# Controller.net
KiCad netlist of a schematic drawn in Altium Designer
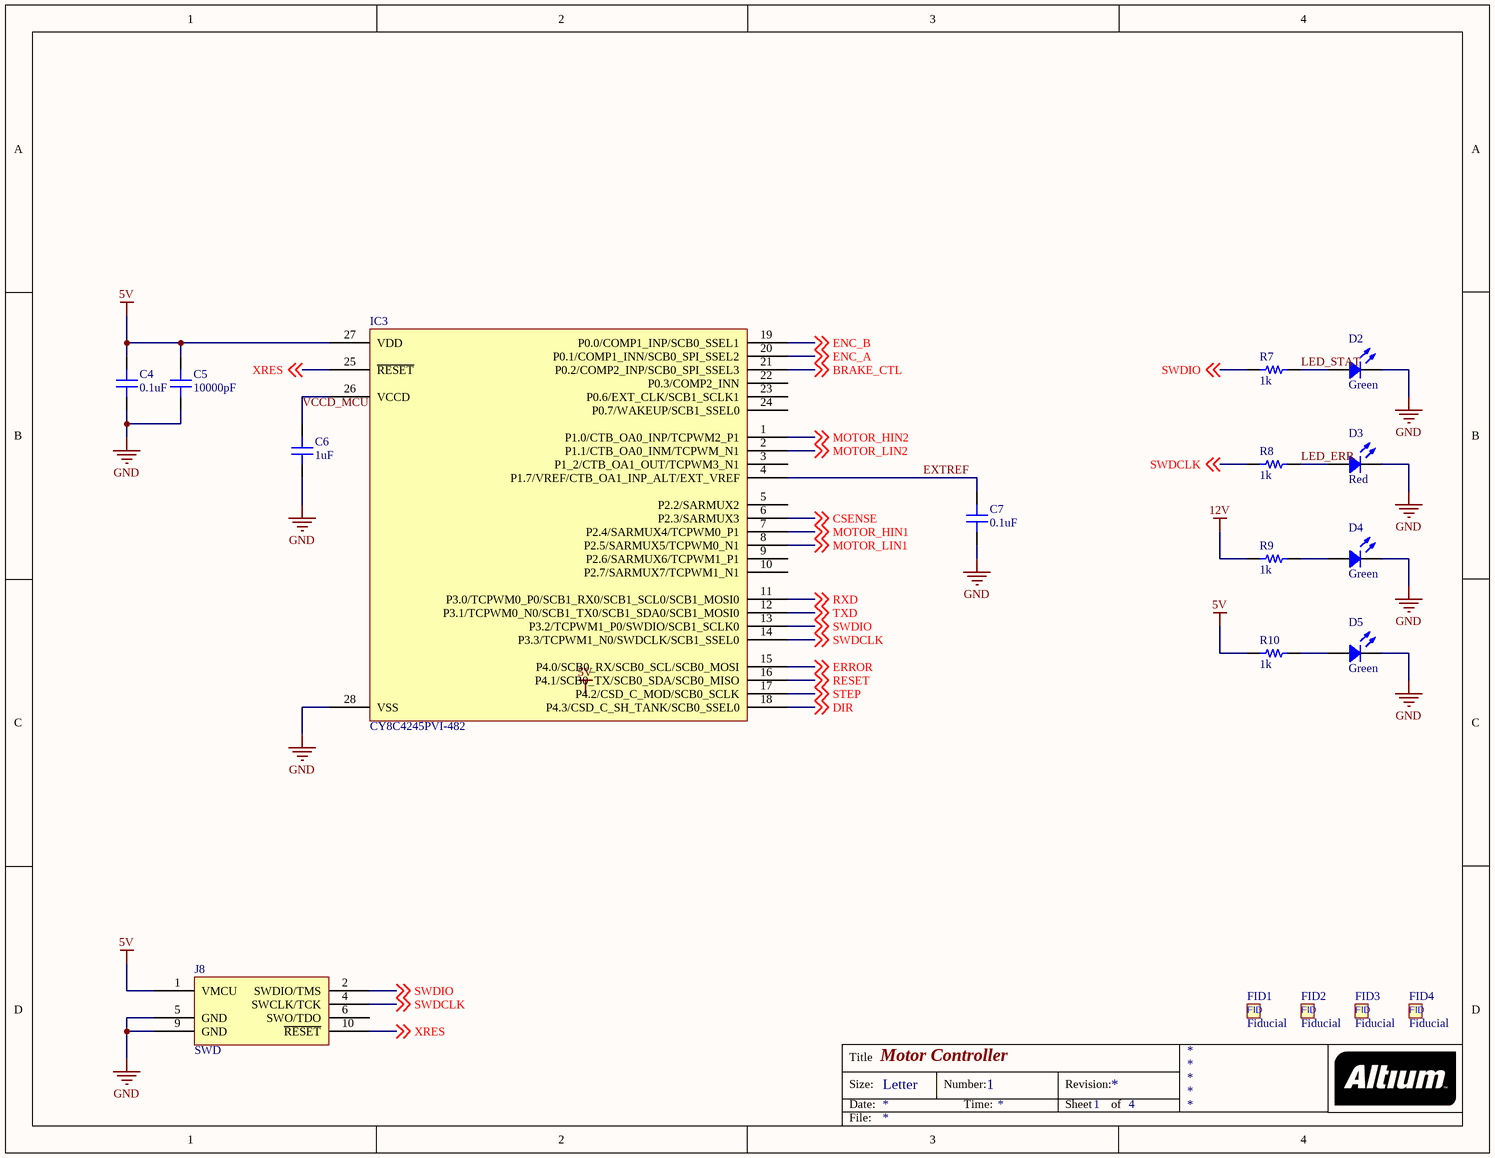
[diagram p0: Controller.SchDoc]

(export (version "E")
  (design (tool "Eeschema 10.0.6"))
  (components
    (comp (ref "C4")
      (value "0.1uF")
      (footprint "CAP 0603/1608")
      (description "CAP CER 0.1UF 16V X7R 0603")
      (fields (field (name "PART NUMBER") "CC0603KPX7R7BB104") (field (name "MANUFACTURER") "Yageo"))
      (libsource (lib "Celestial Library Database") (part "Capacitor"))
    )
    (comp (ref "C5")
      (value "10000pF")
      (footprint "CAP 0603/1608")
      (description "CAP CER 10000PF 50V X7R 0603")
      (fields
        (field (name "PART NUMBER") "CL10B103KB8NCNC")
        (field (name "MANUFACTURER") "Samsung Electro-Mechanics America, Inc.")
      )
      (libsource (lib "Celestial Library Database") (part "Capacitor"))
    )
    (comp (ref "C6")
      (value "1uF")
      (footprint "CAP 0603/1608")
      (description "CAP CER 1UF 16V Y5V 0603")
      (fields (field (name "PART NUMBER") "CC0603ZRY5V7BB105") (field (name "MANUFACTURER") "Yageo"))
      (libsource (lib "Celestial Library Database") (part "Capacitor"))
    )
    (comp (ref "C7")
      (value "0.1uF")
      (footprint "CAP 0603/1608")
      (description "CAP CER 0.1UF 25V X7R 0603")
      (fields (field (name "PART NUMBER") "CC0603JRX7R8BB104") (field (name "MANUFACTURER") "Yageo"))
      (libsource (lib "Celestial Library Database") (part "Capacitor"))
    )
    (comp (ref "D2")
      (value "Green")
      (footprint "LED 0603/1608 GREEN")
      (description "LED GREEN CLEAR 0603 SMD")
      (fields (field (name "PART NUMBER") "LTST-C191KGKT") (field (name "MANUFACTURER") "Lite-On Inc."))
      (libsource (lib "Celestial Library Database") (part "LED"))
    )
    (comp (ref "D3")
      (value "Red")
      (footprint "LED 0603/1608 RED")
      (description "LED RED CLEAR 0603 SMD")
      (fields (field (name "PART NUMBER") "LTST-C191KRKT") (field (name "MANUFACTURER") "Lite-On Inc."))
      (libsource (lib "Celestial Library Database") (part "LED"))
    )
    (comp (ref "D4")
      (value "Green")
      (footprint "LED 0603/1608 GREEN")
      (description "LED GREEN CLEAR 0603 SMD")
      (fields (field (name "PART NUMBER") "LTST-C191KGKT") (field (name "MANUFACTURER") "Lite-On Inc."))
      (libsource (lib "Celestial Library Database") (part "LED"))
    )
    (comp (ref "D5")
      (value "Green")
      (footprint "LED 0603/1608 GREEN")
      (description "LED GREEN CLEAR 0603 SMD")
      (fields (field (name "PART NUMBER") "LTST-C191KGKT") (field (name "MANUFACTURER") "Lite-On Inc."))
      (libsource (lib "Celestial Library Database") (part "LED"))
    )
    (comp (ref "FID1")
      (value "Fiducial")
      (footprint "Fiducial")
      (libsource (lib "Motor Controller") (part "Fiducial"))
    )
    (comp (ref "FID2")
      (value "Fiducial")
      (footprint "Fiducial")
      (libsource (lib "Motor Controller") (part "Fiducial"))
    )
    (comp (ref "FID3")
      (value "Fiducial")
      (footprint "Fiducial")
      (libsource (lib "Motor Controller") (part "Fiducial"))
    )
    (comp (ref "FID4")
      (value "Fiducial")
      (footprint "Fiducial")
      (libsource (lib "Motor Controller") (part "Fiducial"))
    )
    (comp (ref "IC3")
      (value "CY8C4245PVI-482")
      (footprint "CYPRESS SSOP-28 210MIL")
      (description "IC MCU 32BIT 32KB FLASH 28SSOP")
      (fields
        (field (name "MANUFACTURER") "Cypress Semiconductor Corp")
        (field (name "VOLTAGE") "1.71 V ~ 5.5 V")
      )
      (libsource (lib "Celestial Library Database") (part "Cypress CY8C42xx 28SSOP"))
    )
    (comp (ref "J8") (value "SWD") (footprint "10 Pin SWD") (libsource (lib "Motor Controller") (part "SWD")))
    (comp (ref "R7")
      (value "1k")
      (footprint "RES 0603/1608")
      (description "RES SMD 1K OHM 5% 1/10W 0603")
      (fields
        (field (name "PART NUMBER") "ERJ-3GEYJ102V")
        (field (name "MANUFACTURER") "Panasonic Electronic Components")
      )
      (libsource (lib "Celestial Library Database") (part "Resistor"))
    )
    (comp (ref "R8")
      (value "1k")
      (footprint "RES 0603/1608")
      (description "RES SMD 1K OHM 5% 1/10W 0603")
      (fields
        (field (name "PART NUMBER") "ERJ-3GEYJ102V")
        (field (name "MANUFACTURER") "Panasonic Electronic Components")
      )
      (libsource (lib "Celestial Library Database") (part "Resistor"))
    )
    (comp (ref "R9")
      (value "1k")
      (footprint "RES 0603/1608")
      (description "RES SMD 1K OHM 5% 1/10W 0603")
      (fields
        (field (name "PART NUMBER") "ERJ-3GEYJ102V")
        (field (name "MANUFACTURER") "Panasonic Electronic Components")
      )
      (libsource (lib "Celestial Library Database") (part "Resistor"))
    )
    (comp (ref "R10")
      (value "1k")
      (footprint "RES 0603/1608")
      (description "RES SMD 1K OHM 5% 1/10W 0603")
      (fields
        (field (name "PART NUMBER") "ERJ-3GEYJ102V")
        (field (name "MANUFACTURER") "Panasonic Electronic Components")
      )
      (libsource (lib "Celestial Library Database") (part "Resistor"))
    )
  )
  (nets
    (net (code "1") (name "/EXTREF") (class "Default")
      (node (ref "C7") (pin "2") (pinfunction "2_2") (pintype "passive"))
      (node (ref "IC3") (pin "4") (pinfunction "P1.7/VREF/CTB_OA1_INP_ALT/EXT_VREF_4") (pintype "passive"))
    )
    (net (code "2") (name "/LED_ERR") (class "Default")
      (node (ref "D3") (pin "1") (pinfunction "1_1") (pintype "passive"))
      (node (ref "R8") (pin "2") (pinfunction "2_2") (pintype "passive"))
    )
    (net (code "3") (name "/LED_STAT") (class "Default")
      (node (ref "D2") (pin "1") (pinfunction "1_1") (pintype "passive"))
      (node (ref "R7") (pin "2") (pinfunction "2_2") (pintype "passive"))
    )
    (net (code "4") (name "/VCCD_MCU") (class "Default")
      (node (ref "C6") (pin "2") (pinfunction "2_2") (pintype "passive"))
      (node (ref "IC3") (pin "26") (pinfunction "VCCD_26") (pintype "passive"))
    )
    (net (code "5") (name "5V") (class "Default")
      (node (ref "C4") (pin "2") (pinfunction "2_2") (pintype "passive"))
      (node (ref "C5") (pin "2") (pinfunction "2_2") (pintype "passive"))
      (node (ref "IC3") (pin "27") (pinfunction "VDD_27") (pintype "passive"))
      (node (ref "J8") (pin "1") (pinfunction "VMCU_1") (pintype "passive"))
      (node (ref "R10") (pin "1") (pinfunction "1_1") (pintype "passive"))
    )
    (net (code "6") (name "12V") (class "Default")
      (node (ref "R9") (pin "1") (pinfunction "1_1") (pintype "passive"))
    )
    (net (code "7") (name "BRAKE_CTL") (class "Default")
      (node (ref "IC3") (pin "21") (pinfunction "P0.2/COMP2_INP/SCB0_SPI_SSEL3_21") (pintype "passive"))
    )
    (net (code "8") (name "CSENSE") (class "Default")
      (node (ref "IC3") (pin "6") (pinfunction "P2.3/SARMUX3_6") (pintype "passive"))
    )
    (net (code "9") (name "DIR") (class "Default")
      (node (ref "IC3") (pin "18") (pinfunction "P4.3/CSD_C_SH_TANK/SCB0_SSEL0_18") (pintype "passive"))
    )
    (net (code "10") (name "ENC_A") (class "Default")
      (node (ref "IC3") (pin "20") (pinfunction "P0.1/COMP1_INN/SCB0_SPI_SSEL2_20") (pintype "passive"))
    )
    (net (code "11") (name "ENC_B") (class "Default")
      (node (ref "IC3") (pin "19") (pinfunction "P0.0/COMP1_INP/SCB0_SSEL1_19") (pintype "passive"))
    )
    (net (code "12") (name "ERROR") (class "Default")
      (node (ref "IC3") (pin "15") (pinfunction "P4.0/SCB0_RX/SCB0_SCL/SCB0_MOSI_15") (pintype "passive"))
    )
    (net (code "13") (name "GND") (class "Default")
      (node (ref "C4") (pin "1") (pinfunction "1_1") (pintype "passive"))
      (node (ref "C5") (pin "1") (pinfunction "1_1") (pintype "passive"))
      (node (ref "C6") (pin "1") (pinfunction "1_1") (pintype "passive"))
      (node (ref "C7") (pin "1") (pinfunction "1_1") (pintype "passive"))
      (node (ref "D2") (pin "2") (pinfunction "2_2") (pintype "passive"))
      (node (ref "D3") (pin "2") (pinfunction "2_2") (pintype "passive"))
      (node (ref "D4") (pin "2") (pinfunction "2_2") (pintype "passive"))
      (node (ref "D5") (pin "2") (pinfunction "2_2") (pintype "passive"))
      (node (ref "IC3") (pin "28") (pinfunction "VSS_28") (pintype "passive"))
      (node (ref "J8") (pin "5") (pinfunction "GND_5") (pintype "passive"))
      (node (ref "J8") (pin "9") (pinfunction "GND_9") (pintype "passive"))
    )
    (net (code "14") (name "MOTOR_HIN1") (class "Default")
      (node (ref "IC3") (pin "7") (pinfunction "P2.4/SARMUX4/TCPWM0_P1_7") (pintype "passive"))
    )
    (net (code "15") (name "MOTOR_HIN2") (class "Default")
      (node (ref "IC3") (pin "1") (pinfunction "P1.0/CTB_OA0_INP/TCPWM2_P1_1") (pintype "passive"))
    )
    (net (code "16") (name "MOTOR_LIN1") (class "Default")
      (node (ref "IC3") (pin "8") (pinfunction "P2.5/SARMUX5/TCPWM0_N1_8") (pintype "passive"))
    )
    (net (code "17") (name "MOTOR_LIN2") (class "Default")
      (node (ref "IC3") (pin "2") (pinfunction "P1.1/CTB_OA0_INM/TCPWM_N1_2") (pintype "passive"))
    )
    (net (code "18") (name "Net-(D4-Pad1)") (class "Default")
      (node (ref "D4") (pin "1") (pinfunction "1_1") (pintype "passive"))
      (node (ref "R9") (pin "2") (pinfunction "2_2") (pintype "passive"))
    )
    (net (code "19") (name "Net-(D5-Pad1)") (class "Default")
      (node (ref "D5") (pin "1") (pinfunction "1_1") (pintype "passive"))
      (node (ref "R10") (pin "2") (pinfunction "2_2") (pintype "passive"))
    )
    (net (code "20") (name "RESET") (class "Default")
      (node (ref "IC3") (pin "16") (pinfunction "P4.1/SCB0_TX/SCB0_SDA/SCB0_MISO_16") (pintype "passive"))
    )
    (net (code "21") (name "RXD") (class "Default")
      (node (ref "IC3") (pin "11") (pinfunction "P3.0/TCPWM0_P0/SCB1_RX0/SCB1_SCL0/SCB1_MOSI0_11") (pintype "passive"))
    )
    (net (code "22") (name "STEP") (class "Default")
      (node (ref "IC3") (pin "17") (pinfunction "P4.2/CSD_C_MOD/SCB0_SCLK_17") (pintype "passive"))
    )
    (net (code "23") (name "SWDCLK") (class "Default")
      (node (ref "IC3") (pin "14") (pinfunction "P3.3/TCPWM1_N0/SWDCLK/SCB1_SSEL0_14") (pintype "passive"))
      (node (ref "J8") (pin "4") (pinfunction "SWCLK/TCK_4") (pintype "passive"))
      (node (ref "R8") (pin "1") (pinfunction "1_1") (pintype "passive"))
    )
    (net (code "24") (name "SWDIO") (class "Default")
      (node (ref "IC3") (pin "13") (pinfunction "P3.2/TCPWM1_P0/SWDIO/SCB1_SCLK0_13") (pintype "passive"))
      (node (ref "J8") (pin "2") (pinfunction "SWDIO/TMS_2") (pintype "passive"))
      (node (ref "R7") (pin "1") (pinfunction "1_1") (pintype "passive"))
    )
    (net (code "25") (name "TXD") (class "Default")
      (node (ref "IC3") (pin "12") (pinfunction "P3.1/TCPWM0_N0/SCB1_TX0/SCB1_SDA0/SCB1_MOSI0_12") (pintype "passive"))
    )
    (net (code "26") (name "XRES") (class "Default")
      (node (ref "IC3") (pin "25") (pinfunction "~{RESET}_25") (pintype "passive"))
      (node (ref "J8") (pin "10") (pinfunction "~{RESET}_10") (pintype "passive"))
    )
    (net (code "27") (name "unconnected-(IC3-P0.3{slash}COMP2_INN-Pad22)") (class "Default")
      (node (ref "IC3") (pin "22") (pinfunction "P0.3/COMP2_INN_22") (pintype "passive"))
    )
    (net (code "28") (name "unconnected-(IC3-P0.6{slash}EXT_CLK{slash}SCB1_SCLK1-Pad23)") (class "Default")
      (node (ref "IC3") (pin "23") (pinfunction "P0.6/EXT_CLK/SCB1_SCLK1_23") (pintype "passive"))
    )
    (net (code "29") (name "unconnected-(IC3-P0.7{slash}WAKEUP{slash}SCB1_SSEL0-Pad24)") (class "Default")
      (node (ref "IC3") (pin "24") (pinfunction "P0.7/WAKEUP/SCB1_SSEL0_24") (pintype "passive"))
    )
    (net (code "30") (name "unconnected-(IC3-P1_2{slash}CTB_OA1_OUT{slash}TCPWM3_N1-Pad3)") (class "Default")
      (node (ref "IC3") (pin "3") (pinfunction "P1_2/CTB_OA1_OUT/TCPWM3_N1_3") (pintype "passive"))
    )
    (net (code "31") (name "unconnected-(IC3-P2.2{slash}SARMUX2-Pad5)") (class "Default")
      (node (ref "IC3") (pin "5") (pinfunction "P2.2/SARMUX2_5") (pintype "passive"))
    )
    (net (code "32") (name "unconnected-(IC3-P2.6{slash}SARMUX6{slash}TCPWM1_P1-Pad9)") (class "Default")
      (node (ref "IC3") (pin "9") (pinfunction "P2.6/SARMUX6/TCPWM1_P1_9") (pintype "passive"))
    )
    (net (code "33") (name "unconnected-(IC3-P2.7{slash}SARMUX7{slash}TCPWM1_N1-Pad10)") (class "Default")
      (node (ref "IC3") (pin "10") (pinfunction "P2.7/SARMUX7/TCPWM1_N1_10") (pintype "passive"))
    )
    (net (code "34") (name "unconnected-(J8-SWO{slash}TDO-Pad6)") (class "Default")
      (node (ref "J8") (pin "6") (pinfunction "SWO/TDO_6") (pintype "passive"))
    )
  )
)
